# TestNode_V1.net
KiCad netlist of a schematic drawn in EAGLE
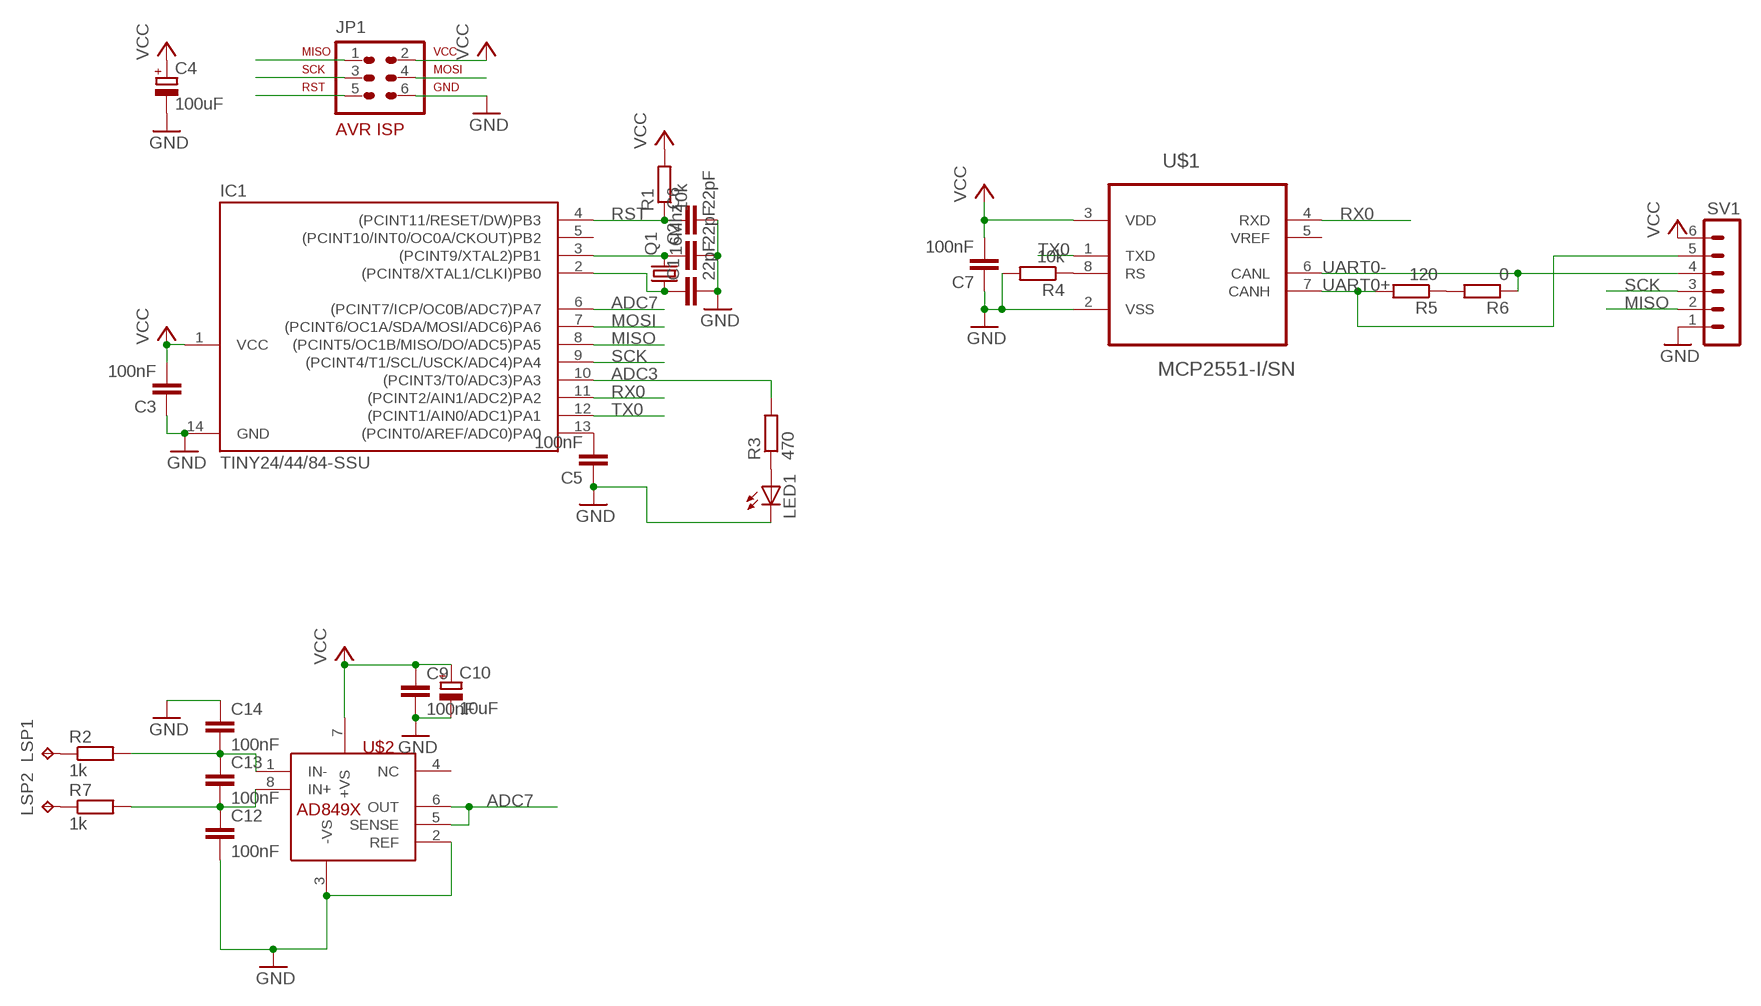
[diagram p0: schematic, sheet 1]

(export (version "E")
  (design (tool "Eeschema 10.0.6"))
  (components
    (comp (ref "C1")
      (value "22pF")
      (footprint "eagle-import:C1206")
      (libsource (lib "eagle-import") (part "C-EUC1206"))
    )
    (comp (ref "C2")
      (value "22pF")
      (footprint "eagle-import:C1206")
      (libsource (lib "eagle-import") (part "C-EUC1206"))
    )
    (comp (ref "C3")
      (value "100nF")
      (footprint "eagle-import:C1206")
      (libsource (lib "eagle-import") (part "C-EUC1206"))
    )
    (comp (ref "C4")
      (value "100uF")
      (footprint "eagle-import:PANASONIC_D")
      (libsource (lib "eagle-import") (part "CPOL-EUD"))
    )
    (comp (ref "C5")
      (value "100nF")
      (footprint "eagle-import:C1206")
      (libsource (lib "eagle-import") (part "C-EUC1206"))
    )
    (comp (ref "C6")
      (value "22pF")
      (footprint "eagle-import:C1206")
      (libsource (lib "eagle-import") (part "C-EUC1206"))
    )
    (comp (ref "C7")
      (value "100nF")
      (footprint "eagle-import:C1206")
      (libsource (lib "eagle-import") (part "C-EUC1206"))
    )
    (comp (ref "C9")
      (value "100nF")
      (footprint "eagle-import:C1206")
      (libsource (lib "eagle-import") (part "C-EUC1206"))
    )
    (comp (ref "C10")
      (value "10uF")
      (footprint "eagle-import:UD-4X5,8_NICHICON")
      (libsource (lib "eagle-import") (part "CPOL-EUUD-4X5,8"))
    )
    (comp (ref "C12")
      (value "100nF")
      (footprint "eagle-import:C0805")
      (libsource (lib "eagle-import") (part "C-EUC0805"))
    )
    (comp (ref "C13")
      (value "100nF")
      (footprint "eagle-import:C0805")
      (libsource (lib "eagle-import") (part "C-EUC0805"))
    )
    (comp (ref "C14")
      (value "100nF")
      (footprint "eagle-import:C0805")
      (libsource (lib "eagle-import") (part "C-EUC0805"))
    )
    (comp (ref "IC1")
      (value "TINY24/44/84-SSU")
      (footprint "eagle-import:SOIC14")
      (libsource (lib "eagle-import") (part "TINY24/44/84-SSU"))
    )
    (comp (ref "JP1")
      (value "AVR-ISP-6VERT")
      (footprint "eagle-import:AVR-ISP-6")
      (libsource (lib "eagle-import") (part "AVR-ISP-6VERT"))
    )
    (comp (ref "LED1")
      (value "LED5MM")
      (footprint "eagle-import:LED5MM")
      (libsource (lib "eagle-import") (part "LED5MM"))
    )
    (comp (ref "LSP1")
      (value "TPTP15R")
      (footprint "eagle-import:TP15R")
      (libsource (lib "eagle-import") (part "TPTP15R"))
    )
    (comp (ref "LSP2")
      (value "TPTP15R")
      (footprint "eagle-import:TP15R")
      (libsource (lib "eagle-import") (part "TPTP15R"))
    )
    (comp (ref "Q1")
      (value "16Mhz")
      (footprint "eagle-import:SM49")
      (libsource (lib "eagle-import") (part "CRYSTALSM49"))
    )
    (comp (ref "R1")
      (value "10k")
      (footprint "eagle-import:R1206")
      (libsource (lib "eagle-import") (part "R-EU_R1206"))
    )
    (comp (ref "R2")
      (value "1k")
      (footprint "eagle-import:R0805")
      (libsource (lib "eagle-import") (part "R-EU_R0805"))
    )
    (comp (ref "R3")
      (value "470")
      (footprint "eagle-import:R1206")
      (libsource (lib "eagle-import") (part "R-EU_R1206"))
    )
    (comp (ref "R4")
      (value "10k")
      (footprint "eagle-import:R1206")
      (libsource (lib "eagle-import") (part "R-EU_R1206"))
    )
    (comp (ref "R5")
      (value "120")
      (footprint "eagle-import:R1206")
      (libsource (lib "eagle-import") (part "R-EU_R1206"))
    )
    (comp (ref "R6")
      (value "0")
      (footprint "eagle-import:R1206")
      (libsource (lib "eagle-import") (part "R-EU_R1206"))
    )
    (comp (ref "R7")
      (value "1k")
      (footprint "eagle-import:R0805")
      (libsource (lib "eagle-import") (part "R-EU_R0805"))
    )
    (comp (ref "SV1")
      (value "MA06-1")
      (footprint "eagle-import:MA06-1")
      (libsource (lib "eagle-import") (part "MA06-1"))
    )
    (comp (ref "U$1")
      (value "MCP2551-I/SN")
      (footprint "eagle-import:SOIC127P600X175-8N")
      (libsource (lib "eagle-import") (part "MCP2551-I/SN"))
    )
    (comp (ref "U$2")
      (value "AD849X")
      (footprint "eagle-import:MSOP8")
      (libsource (lib "eagle-import") (part "AD849X"))
    )
  )
  (nets
    (net (code "1") (name "/ADC3") (class "Default")
      (node (ref "IC1") (pin "10") (pinfunction "(PCINT3/T0/ADC3)PA3_10") (pintype "bidirectional"))
      (node (ref "R3") (pin "2") (pinfunction "2_2") (pintype "passive"))
    )
    (net (code "2") (name "/ADC7") (class "Default")
      (node (ref "IC1") (pin "6") (pinfunction "(PCINT7/ICP/OC0B/ADC7)PA7_6") (pintype "bidirectional"))
      (node (ref "U$2") (pin "5") (pinfunction "SENSE_5") (pintype "input"))
      (node (ref "U$2") (pin "6") (pinfunction "OUT_6") (pintype "output"))
    )
    (net (code "3") (name "/MISO") (class "Default")
      (node (ref "IC1") (pin "8") (pinfunction "(PCINT5/OC1B/MISO/DO/ADC5)PA5_8") (pintype "bidirectional"))
      (node (ref "JP1") (pin "1") (pinfunction "1_1") (pintype "passive"))
      (node (ref "SV1") (pin "2") (pinfunction "2_2") (pintype "passive"))
    )
    (net (code "4") (name "/MOSI") (class "Default")
      (node (ref "IC1") (pin "7") (pinfunction "(PCINT6/OC1A/SDA/MOSI/ADC6)PA6_7") (pintype "bidirectional"))
      (node (ref "JP1") (pin "4") (pinfunction "4_4") (pintype "passive"))
    )
    (net (code "5") (name "/RST") (class "Default")
      (node (ref "C6") (pin "1") (pinfunction "1_1") (pintype "passive"))
      (node (ref "IC1") (pin "4") (pinfunction "(PCINT11/RESET/DW)PB3_4") (pintype "bidirectional"))
      (node (ref "JP1") (pin "5") (pinfunction "5_5") (pintype "passive"))
      (node (ref "R1") (pin "1") (pinfunction "1_1") (pintype "passive"))
    )
    (net (code "6") (name "/RX0") (class "Default")
      (node (ref "IC1") (pin "11") (pinfunction "(PCINT2/AIN1/ADC2)PA2_11") (pintype "bidirectional"))
      (node (ref "U$1") (pin "4") (pinfunction "RXD_4") (pintype "output"))
    )
    (net (code "7") (name "/SCK") (class "Default")
      (node (ref "IC1") (pin "9") (pinfunction "(PCINT4/T1/SCL/USCK/ADC4)PA4_9") (pintype "bidirectional"))
      (node (ref "JP1") (pin "3") (pinfunction "3_3") (pintype "passive"))
      (node (ref "SV1") (pin "3") (pinfunction "3_3") (pintype "passive"))
    )
    (net (code "8") (name "/TX0") (class "Default")
      (node (ref "IC1") (pin "12") (pinfunction "(PCINT1/AIN0/ADC1)PA1_12") (pintype "bidirectional"))
      (node (ref "U$1") (pin "1") (pinfunction "TXD_1") (pintype "input"))
    )
    (net (code "9") (name "/UART0+") (class "Default")
      (node (ref "R5") (pin "2") (pinfunction "2_2") (pintype "passive"))
      (node (ref "SV1") (pin "5") (pinfunction "5_5") (pintype "passive"))
      (node (ref "U$1") (pin "7") (pinfunction "CANH_7") (pintype "bidirectional"))
    )
    (net (code "10") (name "/UART0-") (class "Default")
      (node (ref "R6") (pin "1") (pinfunction "1_1") (pintype "passive"))
      (node (ref "SV1") (pin "4") (pinfunction "4_4") (pintype "passive"))
      (node (ref "U$1") (pin "6") (pinfunction "CANL_6") (pintype "bidirectional"))
    )
    (net (code "11") (name "GND") (class "Default")
      (node (ref "C1") (pin "2") (pinfunction "2_2") (pintype "passive"))
      (node (ref "C10") (pin "-") (pinfunction "-_-") (pintype "passive"))
      (node (ref "C12") (pin "2") (pinfunction "2_2") (pintype "passive"))
      (node (ref "C14") (pin "1") (pinfunction "1_1") (pintype "passive"))
      (node (ref "C2") (pin "2") (pinfunction "2_2") (pintype "passive"))
      (node (ref "C3") (pin "1") (pinfunction "1_1") (pintype "passive"))
      (node (ref "C4") (pin "-") (pinfunction "-_-") (pintype "passive"))
      (node (ref "C5") (pin "1") (pinfunction "1_1") (pintype "passive"))
      (node (ref "C6") (pin "2") (pinfunction "2_2") (pintype "passive"))
      (node (ref "C7") (pin "1") (pinfunction "1_1") (pintype "passive"))
      (node (ref "C9") (pin "2") (pinfunction "2_2") (pintype "passive"))
      (node (ref "IC1") (pin "14") (pinfunction "GND_14") (pintype "power_in"))
      (node (ref "JP1") (pin "6") (pinfunction "6_6") (pintype "passive"))
      (node (ref "LED1") (pin "K") (pinfunction "C_K") (pintype "passive"))
      (node (ref "R4") (pin "2") (pinfunction "2_2") (pintype "passive"))
      (node (ref "SV1") (pin "1") (pinfunction "1_1") (pintype "passive"))
      (node (ref "U$1") (pin "2") (pinfunction "VSS_2") (pintype "passive"))
      (node (ref "U$2") (pin "2") (pinfunction "REF_2") (pintype "input"))
      (node (ref "U$2") (pin "3") (pinfunction "-VS_3") (pintype "power_in"))
    )
    (net (code "12") (name "Net-(IC1-(PCINT0{slash}AREF{slash}ADC0)PA0)") (class "Default")
      (node (ref "C5") (pin "2") (pinfunction "2_2") (pintype "passive"))
      (node (ref "IC1") (pin "13") (pinfunction "(PCINT0/AREF/ADC0)PA0_13") (pintype "bidirectional"))
    )
    (net (code "13") (name "Net-(IC1-(PCINT8{slash}XTAL1{slash}CLKI)PB0)") (class "Default")
      (node (ref "C1") (pin "1") (pinfunction "1_1") (pintype "passive"))
      (node (ref "IC1") (pin "2") (pinfunction "(PCINT8/XTAL1/CLKI)PB0_2") (pintype "bidirectional"))
      (node (ref "Q1") (pin "1") (pinfunction "1_1") (pintype "passive"))
    )
    (net (code "14") (name "Net-(IC1-(PCINT9{slash}XTAL2)PB1)") (class "Default")
      (node (ref "C2") (pin "1") (pinfunction "1_1") (pintype "passive"))
      (node (ref "IC1") (pin "3") (pinfunction "(PCINT9/XTAL2)PB1_3") (pintype "bidirectional"))
      (node (ref "Q1") (pin "2") (pinfunction "2_2") (pintype "passive"))
    )
    (net (code "15") (name "Net-(LED1-PadA)") (class "Default")
      (node (ref "LED1") (pin "A") (pinfunction "A_A") (pintype "passive"))
      (node (ref "R3") (pin "1") (pinfunction "1_1") (pintype "passive"))
    )
    (net (code "16") (name "Net-(LSP1-PadTP)") (class "Default")
      (node (ref "LSP1") (pin "TP") (pinfunction "TP_TP") (pintype "input"))
      (node (ref "R2") (pin "1") (pinfunction "1_1") (pintype "passive"))
    )
    (net (code "17") (name "Net-(LSP2-PadTP)") (class "Default")
      (node (ref "LSP2") (pin "TP") (pinfunction "TP_TP") (pintype "input"))
      (node (ref "R7") (pin "1") (pinfunction "1_1") (pintype "passive"))
    )
    (net (code "18") (name "Net-(R5-Pad1)") (class "Default")
      (node (ref "R5") (pin "1") (pinfunction "1_1") (pintype "passive"))
      (node (ref "R6") (pin "2") (pinfunction "2_2") (pintype "passive"))
    )
    (net (code "19") (name "Net-(U$1-RS)") (class "Default")
      (node (ref "R4") (pin "1") (pinfunction "1_1") (pintype "passive"))
      (node (ref "U$1") (pin "8") (pinfunction "RS_8") (pintype "input"))
    )
    (net (code "20") (name "Net-(U$2-IN+)") (class "Default")
      (node (ref "C12") (pin "1") (pinfunction "1_1") (pintype "passive"))
      (node (ref "C13") (pin "2") (pinfunction "2_2") (pintype "passive"))
      (node (ref "R7") (pin "2") (pinfunction "2_2") (pintype "passive"))
      (node (ref "U$2") (pin "8") (pinfunction "IN+_8") (pintype "input"))
    )
    (net (code "21") (name "Net-(U$2-IN-)") (class "Default")
      (node (ref "C13") (pin "1") (pinfunction "1_1") (pintype "passive"))
      (node (ref "C14") (pin "2") (pinfunction "2_2") (pintype "passive"))
      (node (ref "R2") (pin "2") (pinfunction "2_2") (pintype "passive"))
      (node (ref "U$2") (pin "1") (pinfunction "IN-_1") (pintype "input"))
    )
    (net (code "22") (name "VCC") (class "Default")
      (node (ref "C10") (pin "+") (pinfunction "+_+") (pintype "passive"))
      (node (ref "C3") (pin "2") (pinfunction "2_2") (pintype "passive"))
      (node (ref "C4") (pin "+") (pinfunction "+_+") (pintype "passive"))
      (node (ref "C7") (pin "2") (pinfunction "2_2") (pintype "passive"))
      (node (ref "C9") (pin "1") (pinfunction "1_1") (pintype "passive"))
      (node (ref "IC1") (pin "1") (pinfunction "VCC_1") (pintype "power_in"))
      (node (ref "JP1") (pin "2") (pinfunction "2_2") (pintype "passive"))
      (node (ref "R1") (pin "2") (pinfunction "2_2") (pintype "passive"))
      (node (ref "SV1") (pin "6") (pinfunction "6_6") (pintype "passive"))
      (node (ref "U$1") (pin "3") (pinfunction "VDD_3") (pintype "power_in"))
      (node (ref "U$2") (pin "7") (pinfunction "+VS_7") (pintype "power_in"))
    )
    (net (code "23") (name "unconnected-(IC1-(PCINT10{slash}INT0{slash}OC0A{slash}CKOUT)PB2-Pad5)") (class "Default")
      (node (ref "IC1") (pin "5") (pinfunction "(PCINT10/INT0/OC0A/CKOUT)PB2_5") (pintype "bidirectional"))
    )
    (net (code "24") (name "unconnected-(U$1-VREF-Pad5)") (class "Default")
      (node (ref "U$1") (pin "5") (pinfunction "VREF_5") (pintype "output"))
    )
    (net (code "25") (name "unconnected-(U$2-NC-Pad4)") (class "Default")
      (node (ref "U$2") (pin "4") (pinfunction "NC_4") (pintype "no_connect"))
    )
  )
)
